# CPU_ETH_RGMII1_SW.net
KiCad netlist of a schematic drawn in Altium Designer
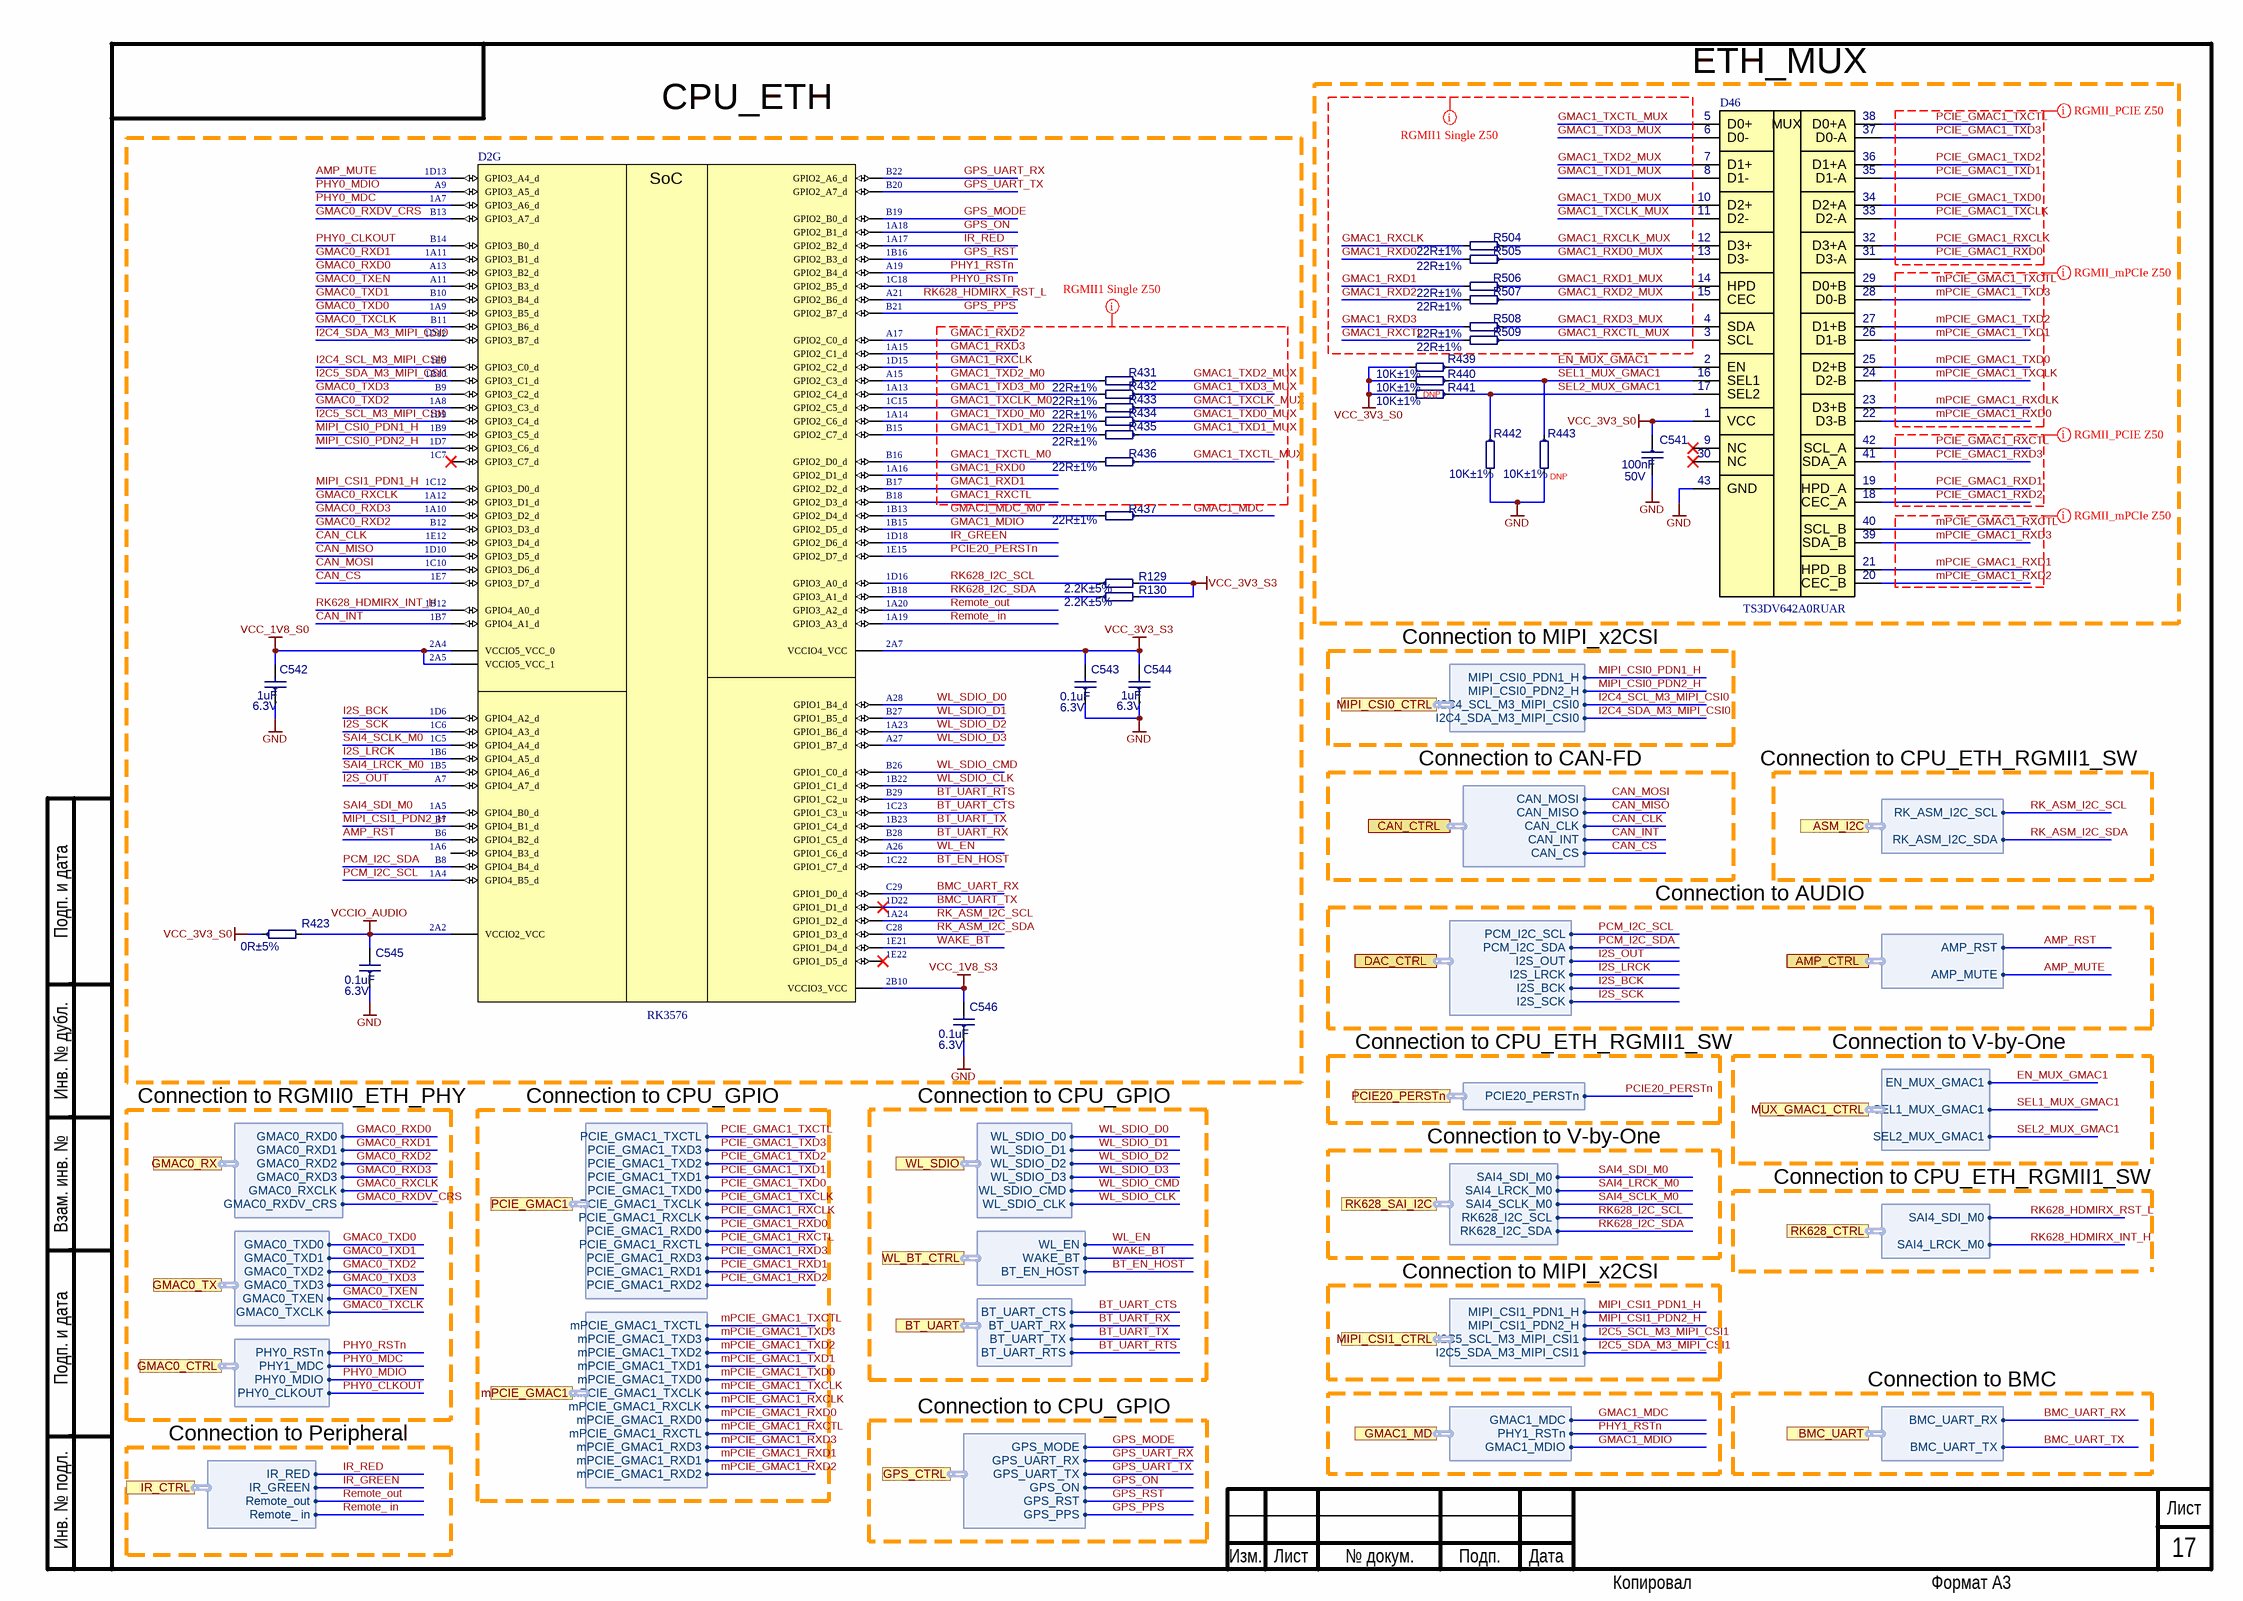
[diagram p0: CPU_ETH_RGMII1_SW.SchDoc]

(export (version "E")
  (design (tool "Eeschema 10.0.6"))
  (components
    (comp (ref "C541")
      (value "100nF")
      (footprint "C0402")
      (description "Ceramic Capacitor 0402 100nF ±10% 50V X7R")
      (fields
        (field (name "VOLTAGE") "50V")
        (field (name "PART NUMBER") "0402-X7R-50V-0.1uF±10%")
        (field (name "TOLERANCE") "10%")
      )
      (libsource (lib "ATB") (part "C"))
    )
    (comp (ref "C542")
      (value "1uF")
      (footprint "C0201")
      (fields
        (field (name "VOLTAGE") "6.3V")
        (field (name "PART NUMBER") "0201-X5R-6.3V-1uF±20%")
        (field (name "TOLERANCE") "20%")
        (field (name "MANUFACTURER") "Murata Electronics")
      )
      (libsource (lib "ATB") (part "C"))
    )
    (comp (ref "C543")
      (value "0.1uF")
      (footprint "C0201")
      (fields
        (field (name "VOLTAGE") "6.3V")
        (field (name "PART NUMBER") "0201-X5R-6.3V-0.1uF±10%")
        (field (name "TOLERANCE") "10%")
        (field (name "MANUFACTURER") "Yageo")
      )
      (libsource (lib "ATB") (part "C"))
    )
    (comp (ref "C544")
      (value "1uF")
      (footprint "C0201")
      (fields
        (field (name "VOLTAGE") "6.3V")
        (field (name "PART NUMBER") "0201-X5R-6.3V-1uF±20%")
        (field (name "TOLERANCE") "20%")
        (field (name "MANUFACTURER") "Murata Electronics")
      )
      (libsource (lib "ATB") (part "C"))
    )
    (comp (ref "C545")
      (value "0.1uF")
      (footprint "C0201")
      (fields
        (field (name "VOLTAGE") "6.3V")
        (field (name "PART NUMBER") "0201-X5R-6.3V-0.1uF±10%")
        (field (name "TOLERANCE") "10%")
        (field (name "MANUFACTURER") "Yageo")
      )
      (libsource (lib "ATB") (part "C"))
    )
    (comp (ref "C546")
      (value "0.1uF")
      (footprint "C0201")
      (fields
        (field (name "VOLTAGE") "6.3V")
        (field (name "PART NUMBER") "0201-X5R-6.3V-0.1uF±10%")
        (field (name "TOLERANCE") "10%")
        (field (name "MANUFACTURER") "Yageo")
      )
      (libsource (lib "ATB") (part "C"))
    )
    (comp (ref "D2")
      (value "RK3576")
      (footprint "BGAFCCSP698L")
      (description "SoC 4xCortex-A72@2.2Ghz+4xCortex-A53@2Ghz, LPDDR4/4X/5/5X, SDIO/eMMC/UFS/FSPI, BGA 16.1x17.2x1.0mm")
      (fields (field (name "MANUFACTURER") "Rockship"))
      (libsource (lib "ATB") (part "RK3576"))
    )
    (comp (ref "D46")
      (value "TS3DV642A0RUAR")
      (footprint "TS3DV642A0RUAR")
      (description "6-Gbps 12-channel differential 1-to-2 and 2-to-1 mux for DVI 1.0/ DisplayPort 1.4 /HDMI 2.0")
      (fields (field (name "MANUFACTURER") "TI"))
      (libsource (lib "LIB_RK") (part "TS3DV642A0RUAR"))
    )
    (comp (ref "R129")
      (value "2.2K±5%")
      (footprint "R0402")
      (fields
        (field (name "PART NUMBER") "0402-0.0625W-2.2K-100ppm±5%")
        (field (name "TOLERANCE") "5%")
        (field (name "MANUFACTURER") "Yageo")
      )
      (libsource (lib "ATB") (part "R"))
    )
    (comp (ref "R130")
      (value "2.2K±5%")
      (footprint "R0402")
      (fields
        (field (name "PART NUMBER") "0402-0.0625W-2.2K-100ppm±5%")
        (field (name "TOLERANCE") "5%")
        (field (name "MANUFACTURER") "Yageo")
      )
      (libsource (lib "ATB") (part "R"))
    )
    (comp (ref "R423")
      (value "0R±5%")
      (footprint "R0402")
      (fields
        (field (name "PART NUMBER") "0402-0.0625W-0R-100ppm±5%")
        (field (name "TOLERANCE") "5%")
        (field (name "MANUFACTURER") "Yageo")
      )
      (libsource (lib "ATB") (part "R"))
    )
    (comp (ref "R431")
      (value "22R±1%")
      (footprint "R0402")
      (description "Chip Resistor 0402 22Ω ±1% 50V ±100ppm/℃ Thick Film")
      (fields (field (name "PART NUMBER") "0402-0.0625W-22R-100ppm±1%") (field (name "TOLERANCE") "1%"))
      (libsource (lib "ATB") (part "R"))
    )
    (comp (ref "R432")
      (value "22R±1%")
      (footprint "R0402")
      (description "Chip Resistor 0402 22Ω ±1% 50V ±100ppm/℃ Thick Film")
      (fields (field (name "PART NUMBER") "0402-0.0625W-22R-100ppm±1%") (field (name "TOLERANCE") "1%"))
      (libsource (lib "ATB") (part "R"))
    )
    (comp (ref "R433")
      (value "22R±1%")
      (footprint "R0402")
      (description "Chip Resistor 0402 22Ω ±1% 50V ±100ppm/℃ Thick Film")
      (fields (field (name "PART NUMBER") "0402-0.0625W-22R-100ppm±1%") (field (name "TOLERANCE") "1%"))
      (libsource (lib "ATB") (part "R"))
    )
    (comp (ref "R434")
      (value "22R±1%")
      (footprint "R0402")
      (description "Chip Resistor 0402 22Ω ±1% 50V ±100ppm/℃ Thick Film")
      (fields (field (name "PART NUMBER") "0402-0.0625W-22R-100ppm±1%") (field (name "TOLERANCE") "1%"))
      (libsource (lib "ATB") (part "R"))
    )
    (comp (ref "R435")
      (value "22R±1%")
      (footprint "R0402")
      (description "Chip Resistor 0402 22Ω ±1% 50V ±100ppm/℃ Thick Film")
      (fields (field (name "PART NUMBER") "0402-0.0625W-22R-100ppm±1%") (field (name "TOLERANCE") "1%"))
      (libsource (lib "ATB") (part "R"))
    )
    (comp (ref "R436")
      (value "22R±1%")
      (footprint "R0402")
      (description "Chip Resistor 0402 22Ω ±1% 50V ±100ppm/℃ Thick Film")
      (fields (field (name "PART NUMBER") "0402-0.0625W-22R-100ppm±1%") (field (name "TOLERANCE") "1%"))
      (libsource (lib "ATB") (part "R"))
    )
    (comp (ref "R437")
      (value "22R±1%")
      (footprint "R0402")
      (description "Chip Resistor 0402 22Ω ±1% 50V ±100ppm/℃ Thick Film")
      (fields (field (name "PART NUMBER") "0402-0.0625W-22R-100ppm±1%") (field (name "TOLERANCE") "1%"))
      (libsource (lib "ATB") (part "R"))
    )
    (comp (ref "R439")
      (value "10K±1%")
      (footprint "R0402")
      (description "Chip Resistor 0402 10kΩ ±1% 50V ±100ppm/℃ Thick Film")
      (fields (field (name "PART NUMBER") "0402-0.0625W-10K-100ppm±1%") (field (name "TOLERANCE") "1%"))
      (libsource (lib "ATB") (part "R"))
    )
    (comp (ref "R440")
      (value "10K±1%")
      (footprint "R0402")
      (description "Chip Resistor 0402 10kΩ ±1% 50V ±100ppm/℃ Thick Film")
      (fields (field (name "PART NUMBER") "0402-0.0625W-10K-100ppm±1%") (field (name "TOLERANCE") "1%"))
      (libsource (lib "ATB") (part "R"))
    )
    (comp (ref "R441")
      (value "10K±1%")
      (footprint "R0402")
      (description "Chip Resistor 0402 10kΩ ±1% 50V ±100ppm/℃ Thick Film")
      (fields (field (name "PART NUMBER") "0402-0.0625W-10K-100ppm±1%") (field (name "TOLERANCE") "1%"))
      (libsource (lib "ATB") (part "R"))
    )
    (comp (ref "R442")
      (value "10K±1%")
      (footprint "R0402")
      (description "Chip Resistor 0402 10kΩ ±1% 50V ±100ppm/℃ Thick Film")
      (fields (field (name "PART NUMBER") "0402-0.0625W-10K-100ppm±1%") (field (name "TOLERANCE") "1%"))
      (libsource (lib "ATB") (part "R"))
    )
    (comp (ref "R443")
      (value "10K±1%")
      (footprint "R0402")
      (description "Chip Resistor 0402 10kΩ ±1% 50V ±100ppm/℃ Thick Film")
      (fields (field (name "PART NUMBER") "0402-0.0625W-10K-100ppm±1%") (field (name "TOLERANCE") "1%"))
      (libsource (lib "ATB") (part "R"))
    )
    (comp (ref "R504")
      (value "22R±1%")
      (footprint "R0402")
      (description "Chip Resistor 0402 22Ω ±1% 50V ±100ppm/℃ Thick Film")
      (fields (field (name "PART NUMBER") "0402-0.0625W-22R-100ppm±1%") (field (name "TOLERANCE") "1%"))
      (libsource (lib "ATB") (part "R"))
    )
    (comp (ref "R505")
      (value "22R±1%")
      (footprint "R0402")
      (description "Chip Resistor 0402 22Ω ±1% 50V ±100ppm/℃ Thick Film")
      (fields (field (name "PART NUMBER") "0402-0.0625W-22R-100ppm±1%") (field (name "TOLERANCE") "1%"))
      (libsource (lib "ATB") (part "R"))
    )
    (comp (ref "R506")
      (value "22R±1%")
      (footprint "R0402")
      (description "Chip Resistor 0402 22Ω ±1% 50V ±100ppm/℃ Thick Film")
      (fields (field (name "PART NUMBER") "0402-0.0625W-22R-100ppm±1%") (field (name "TOLERANCE") "1%"))
      (libsource (lib "ATB") (part "R"))
    )
    (comp (ref "R507")
      (value "22R±1%")
      (footprint "R0402")
      (description "Chip Resistor 0402 22Ω ±1% 50V ±100ppm/℃ Thick Film")
      (fields (field (name "PART NUMBER") "0402-0.0625W-22R-100ppm±1%") (field (name "TOLERANCE") "1%"))
      (libsource (lib "ATB") (part "R"))
    )
    (comp (ref "R508")
      (value "22R±1%")
      (footprint "R0402")
      (description "Chip Resistor 0402 22Ω ±1% 50V ±100ppm/℃ Thick Film")
      (fields (field (name "PART NUMBER") "0402-0.0625W-22R-100ppm±1%") (field (name "TOLERANCE") "1%"))
      (libsource (lib "ATB") (part "R"))
    )
    (comp (ref "R509")
      (value "22R±1%")
      (footprint "R0402")
      (description "Chip Resistor 0402 22Ω ±1% 50V ±100ppm/℃ Thick Film")
      (fields (field (name "PART NUMBER") "0402-0.0625W-22R-100ppm±1%") (field (name "TOLERANCE") "1%"))
      (libsource (lib "ATB") (part "R"))
    )
  )
  (nets
    (net (code "22") (name "/AMP_MUTE") (class "Default")
      (node (ref "D2") (pin "1D13") (pinfunction "GPIO3_A4_d_1D13") (pintype "bidirectional"))
    )
    (net (code "23") (name "/AMP_RST") (class "Default")
      (node (ref "D2") (pin "B6") (pinfunction "GPIO4_B2_d_B6") (pintype "bidirectional"))
    )
    (net (code "24") (name "/BMC_UART_RX") (class "Default")
      (node (ref "D2") (pin "C29") (pinfunction "GPIO1_D0_d_C29") (pintype "bidirectional"))
    )
    (net (code "25") (name "/BMC_UART_TX") (class "Default")
      (node (ref "D2") (pin "1D22") (pinfunction "GPIO1_D1_d_1D22") (pintype "bidirectional+no_connect"))
    )
    (net (code "26") (name "/BT_EN_HOST") (class "Default")
      (node (ref "D2") (pin "1C22") (pinfunction "GPIO1_C7_d_1C22") (pintype "bidirectional"))
    )
    (net (code "27") (name "/BT_UART_CTS") (class "Default")
      (node (ref "D2") (pin "1C23") (pinfunction "GPIO1_C3_u_1C23") (pintype "bidirectional"))
    )
    (net (code "28") (name "/BT_UART_RTS") (class "Default")
      (node (ref "D2") (pin "B29") (pinfunction "GPIO1_C2_u_B29") (pintype "bidirectional"))
    )
    (net (code "29") (name "/BT_UART_RX") (class "Default")
      (node (ref "D2") (pin "B28") (pinfunction "GPIO1_C5_d_B28") (pintype "bidirectional"))
    )
    (net (code "30") (name "/BT_UART_TX") (class "Default")
      (node (ref "D2") (pin "1B23") (pinfunction "GPIO1_C4_d_1B23") (pintype "bidirectional"))
    )
    (net (code "31") (name "/CAN_CLK") (class "Default")
      (node (ref "D2") (pin "1E12") (pinfunction "GPIO3_D4_d_1E12") (pintype "bidirectional"))
    )
    (net (code "32") (name "/CAN_CS") (class "Default")
      (node (ref "D2") (pin "1E7") (pinfunction "GPIO3_D7_d_1E7") (pintype "bidirectional"))
    )
    (net (code "33") (name "/CAN_INT") (class "Default")
      (node (ref "D2") (pin "1B7") (pinfunction "GPIO4_A1_d_1B7") (pintype "bidirectional"))
    )
    (net (code "34") (name "/CAN_MISO") (class "Default")
      (node (ref "D2") (pin "1D10") (pinfunction "GPIO3_D5_d_1D10") (pintype "bidirectional"))
    )
    (net (code "35") (name "/CAN_MOSI") (class "Default")
      (node (ref "D2") (pin "1C10") (pinfunction "GPIO3_D6_d_1C10") (pintype "bidirectional"))
    )
    (net (code "36") (name "/EN_MUX_GMAC1") (class "Default")
      (node (ref "D46") (pin "2") (pinfunction "EN_2") (pintype "passive"))
      (node (ref "R439") (pin "1") (pinfunction "1_1") (pintype "passive"))
    )
    (net (code "37") (name "/GMAC0_RXCLK") (class "Default")
      (node (ref "D2") (pin "1A12") (pinfunction "GPIO3_D1_d_1A12") (pintype "bidirectional"))
    )
    (net (code "38") (name "/GMAC0_RXD0") (class "Default")
      (node (ref "D2") (pin "A13") (pinfunction "GPIO3_B2_d_A13") (pintype "bidirectional"))
    )
    (net (code "39") (name "/GMAC0_RXD1") (class "Default")
      (node (ref "D2") (pin "1A11") (pinfunction "GPIO3_B1_d_1A11") (pintype "bidirectional"))
    )
    (net (code "40") (name "/GMAC0_RXD2") (class "Default")
      (node (ref "D2") (pin "B12") (pinfunction "GPIO3_D3_d_B12") (pintype "bidirectional"))
    )
    (net (code "41") (name "/GMAC0_RXD3") (class "Default")
      (node (ref "D2") (pin "1A10") (pinfunction "GPIO3_D2_d_1A10") (pintype "bidirectional"))
    )
    (net (code "42") (name "/GMAC0_RXDV_CRS") (class "Default")
      (node (ref "D2") (pin "B13") (pinfunction "GPIO3_A7_d_B13") (pintype "bidirectional"))
    )
    (net (code "43") (name "/GMAC0_TXCLK") (class "Default")
      (node (ref "D2") (pin "B11") (pinfunction "GPIO3_B6_d_B11") (pintype "bidirectional"))
    )
    (net (code "44") (name "/GMAC0_TXD0") (class "Default")
      (node (ref "D2") (pin "1A9") (pinfunction "GPIO3_B5_d_1A9") (pintype "bidirectional"))
    )
    (net (code "45") (name "/GMAC0_TXD1") (class "Default")
      (node (ref "D2") (pin "B10") (pinfunction "GPIO3_B4_d_B10") (pintype "bidirectional"))
    )
    (net (code "46") (name "/GMAC0_TXD2") (class "Default")
      (node (ref "D2") (pin "1A8") (pinfunction "GPIO3_C3_d_1A8") (pintype "bidirectional"))
    )
    (net (code "47") (name "/GMAC0_TXD3") (class "Default")
      (node (ref "D2") (pin "B9") (pinfunction "GPIO3_C2_d_B9") (pintype "bidirectional"))
    )
    (net (code "48") (name "/GMAC0_TXEN") (class "Default")
      (node (ref "D2") (pin "A11") (pinfunction "GPIO3_B3_d_A11") (pintype "bidirectional"))
    )
    (net (code "49") (name "/GMAC1_MDC") (class "Default")
      (node (ref "R437") (pin "1") (pinfunction "1_1") (pintype "passive"))
    )
    (net (code "50") (name "/GMAC1_MDC_M0") (class "Default")
      (node (ref "D2") (pin "1B13") (pinfunction "GPIO2_D4_d_1B13") (pintype "bidirectional"))
      (node (ref "R437") (pin "2") (pinfunction "2_2") (pintype "passive"))
    )
    (net (code "51") (name "/GMAC1_MDIO") (class "Default")
      (node (ref "D2") (pin "1B15") (pinfunction "GPIO2_D5_d_1B15") (pintype "bidirectional"))
    )
    (net (code "52") (name "/GMAC1_RXCLK") (class "Default")
      (node (ref "D2") (pin "1D15") (pinfunction "GPIO2_C2_d_1D15") (pintype "bidirectional"))
      (node (ref "R504") (pin "2") (pinfunction "2_2") (pintype "passive"))
    )
    (net (code "53") (name "/GMAC1_RXCLK_MUX") (class "Default")
      (node (ref "D46") (pin "12") (pinfunction "D3+_12") (pintype "passive"))
      (node (ref "R504") (pin "1") (pinfunction "1_1") (pintype "passive"))
    )
    (net (code "54") (name "/GMAC1_RXCTL") (class "Default")
      (node (ref "D2") (pin "B18") (pinfunction "GPIO2_D3_d_B18") (pintype "bidirectional"))
      (node (ref "R509") (pin "2") (pinfunction "2_2") (pintype "passive"))
    )
    (net (code "55") (name "/GMAC1_RXCTL_MUX") (class "Default")
      (node (ref "D46") (pin "3") (pinfunction "SCL_3") (pintype "passive"))
      (node (ref "R509") (pin "1") (pinfunction "1_1") (pintype "passive"))
    )
    (net (code "56") (name "/GMAC1_RXD0") (class "Default")
      (node (ref "D2") (pin "1A16") (pinfunction "GPIO2_D1_d_1A16") (pintype "bidirectional"))
      (node (ref "R505") (pin "2") (pinfunction "2_2") (pintype "passive"))
    )
    (net (code "57") (name "/GMAC1_RXD0_MUX") (class "Default")
      (node (ref "D46") (pin "13") (pinfunction "D3-_13") (pintype "passive"))
      (node (ref "R505") (pin "1") (pinfunction "1_1") (pintype "passive"))
    )
    (net (code "58") (name "/GMAC1_RXD1") (class "Default")
      (node (ref "D2") (pin "B17") (pinfunction "GPIO2_D2_d_B17") (pintype "bidirectional"))
      (node (ref "R506") (pin "2") (pinfunction "2_2") (pintype "passive"))
    )
    (net (code "59") (name "/GMAC1_RXD1_MUX") (class "Default")
      (node (ref "D46") (pin "14") (pinfunction "HPD_14") (pintype "passive"))
      (node (ref "R506") (pin "1") (pinfunction "1_1") (pintype "passive"))
    )
    (net (code "60") (name "/GMAC1_RXD2") (class "Default")
      (node (ref "D2") (pin "A17") (pinfunction "GPIO2_C0_d_A17") (pintype "bidirectional"))
      (node (ref "R507") (pin "2") (pinfunction "2_2") (pintype "passive"))
    )
    (net (code "61") (name "/GMAC1_RXD2_MUX") (class "Default")
      (node (ref "D46") (pin "15") (pinfunction "CEC_15") (pintype "passive"))
      (node (ref "R507") (pin "1") (pinfunction "1_1") (pintype "passive"))
    )
    (net (code "62") (name "/GMAC1_RXD3") (class "Default")
      (node (ref "D2") (pin "1A15") (pinfunction "GPIO2_C1_d_1A15") (pintype "bidirectional"))
      (node (ref "R508") (pin "2") (pinfunction "2_2") (pintype "passive"))
    )
    (net (code "63") (name "/GMAC1_RXD3_MUX") (class "Default")
      (node (ref "D46") (pin "4") (pinfunction "SDA_4") (pintype "passive"))
      (node (ref "R508") (pin "1") (pinfunction "1_1") (pintype "passive"))
    )
    (net (code "64") (name "/GMAC1_TXCLK_M0") (class "Default")
      (node (ref "D2") (pin "1C15") (pinfunction "GPIO2_C5_d_1C15") (pintype "bidirectional"))
      (node (ref "R433") (pin "2") (pinfunction "2_2") (pintype "passive"))
    )
    (net (code "65") (name "/GMAC1_TXCLK_MUX") (class "Default")
      (node (ref "D46") (pin "11") (pinfunction "D2-_11") (pintype "passive"))
      (node (ref "R433") (pin "1") (pinfunction "1_1") (pintype "passive"))
    )
    (net (code "66") (name "/GMAC1_TXCTL_M0") (class "Default")
      (node (ref "D2") (pin "B16") (pinfunction "GPIO2_D0_d_B16") (pintype "bidirectional"))
      (node (ref "R436") (pin "2") (pinfunction "2_2") (pintype "passive"))
    )
    (net (code "67") (name "/GMAC1_TXCTL_MUX") (class "Default")
      (node (ref "D46") (pin "5") (pinfunction "D0+_5") (pintype "passive"))
      (node (ref "R436") (pin "1") (pinfunction "1_1") (pintype "passive"))
    )
    (net (code "68") (name "/GMAC1_TXD0_M0") (class "Default")
      (node (ref "D2") (pin "1A14") (pinfunction "GPIO2_C6_d_1A14") (pintype "bidirectional"))
      (node (ref "R434") (pin "2") (pinfunction "2_2") (pintype "passive"))
    )
    (net (code "69") (name "/GMAC1_TXD0_MUX") (class "Default")
      (node (ref "D46") (pin "10") (pinfunction "D2+_10") (pintype "passive"))
      (node (ref "R434") (pin "1") (pinfunction "1_1") (pintype "passive"))
    )
    (net (code "70") (name "/GMAC1_TXD1_M0") (class "Default")
      (node (ref "D2") (pin "B15") (pinfunction "GPIO2_C7_d_B15") (pintype "bidirectional"))
      (node (ref "R435") (pin "2") (pinfunction "2_2") (pintype "passive"))
    )
    (net (code "71") (name "/GMAC1_TXD1_MUX") (class "Default")
      (node (ref "D46") (pin "8") (pinfunction "D1-_8") (pintype "passive"))
      (node (ref "R435") (pin "1") (pinfunction "1_1") (pintype "passive"))
    )
    (net (code "72") (name "/GMAC1_TXD2_M0") (class "Default")
      (node (ref "D2") (pin "A15") (pinfunction "GPIO2_C3_d_A15") (pintype "bidirectional"))
      (node (ref "R431") (pin "2") (pinfunction "2_2") (pintype "passive"))
    )
    (net (code "73") (name "/GMAC1_TXD2_MUX") (class "Default")
      (node (ref "D46") (pin "7") (pinfunction "D1+_7") (pintype "passive"))
      (node (ref "R431") (pin "1") (pinfunction "1_1") (pintype "passive"))
    )
    (net (code "74") (name "/GMAC1_TXD3_M0") (class "Default")
      (node (ref "D2") (pin "1A13") (pinfunction "GPIO2_C4_d_1A13") (pintype "bidirectional"))
      (node (ref "R432") (pin "2") (pinfunction "2_2") (pintype "passive"))
    )
    (net (code "75") (name "/GMAC1_TXD3_MUX") (class "Default")
      (node (ref "D46") (pin "6") (pinfunction "D0-_6") (pintype "passive"))
      (node (ref "R432") (pin "1") (pinfunction "1_1") (pintype "passive"))
    )
    (net (code "76") (name "/GPS_MODE") (class "Default")
      (node (ref "D2") (pin "B19") (pinfunction "GPIO2_B0_d_B19") (pintype "bidirectional"))
    )
    (net (code "77") (name "/GPS_ON") (class "Default")
      (node (ref "D2") (pin "1A18") (pinfunction "GPIO2_B1_d_1A18") (pintype "bidirectional"))
    )
    (net (code "78") (name "/GPS_PPS") (class "Default")
      (node (ref "D2") (pin "B21") (pinfunction "GPIO2_B7_d_B21") (pintype "bidirectional"))
    )
    (net (code "79") (name "/GPS_RST") (class "Default")
      (node (ref "D2") (pin "1B16") (pinfunction "GPIO2_B3_d_1B16") (pintype "bidirectional"))
    )
    (net (code "80") (name "/GPS_UART_RX") (class "Default")
      (node (ref "D2") (pin "B22") (pinfunction "GPIO2_A6_d_B22") (pintype "bidirectional"))
    )
    (net (code "81") (name "/GPS_UART_TX") (class "Default")
      (node (ref "D2") (pin "B20") (pinfunction "GPIO2_A7_d_B20") (pintype "bidirectional"))
    )
    (net (code "82") (name "/I2C4_SCL_M3_MIPI_CSI0") (class "Default")
      (node (ref "D2") (pin "1E9") (pinfunction "GPIO3_C0_d_1E9") (pintype "bidirectional"))
    )
    (net (code "83") (name "/I2C4_SDA_M3_MIPI_CSI0") (class "Default")
      (node (ref "D2") (pin "1D12") (pinfunction "GPIO3_B7_d_1D12") (pintype "bidirectional"))
    )
    (net (code "84") (name "/I2C5_SCL_M3_MIPI_CSI1") (class "Default")
      (node (ref "D2") (pin "1D9") (pinfunction "GPIO3_C4_d_1D9") (pintype "bidirectional"))
    )
    (net (code "85") (name "/I2C5_SDA_M3_MIPI_CSI1") (class "Default")
      (node (ref "D2") (pin "1B10") (pinfunction "GPIO3_C1_d_1B10") (pintype "bidirectional"))
    )
    (net (code "86") (name "/I2S_BCK") (class "Default")
      (node (ref "D2") (pin "1D6") (pinfunction "GPIO4_A2_d_1D6") (pintype "bidirectional"))
    )
    (net (code "87") (name "/I2S_LRCK") (class "Default")
      (node (ref "D2") (pin "1B6") (pinfunction "GPIO4_A5_d_1B6") (pintype "bidirectional"))
    )
    (net (code "88") (name "/I2S_OUT") (class "Default")
      (node (ref "D2") (pin "A7") (pinfunction "GPIO4_A7_d_A7") (pintype "bidirectional"))
    )
    (net (code "89") (name "/I2S_SCK") (class "Default")
      (node (ref "D2") (pin "1C6") (pinfunction "GPIO4_A3_d_1C6") (pintype "bidirectional"))
    )
    (net (code "90") (name "/IR_GREEN") (class "Default")
      (node (ref "D2") (pin "1D18") (pinfunction "GPIO2_D6_d_1D18") (pintype "bidirectional"))
    )
    (net (code "91") (name "/IR_RED") (class "Default")
      (node (ref "D2") (pin "1A17") (pinfunction "GPIO2_B2_d_1A17") (pintype "bidirectional"))
    )
    (net (code "92") (name "/MIPI_CSI0_PDN1_H") (class "Default")
      (node (ref "D2") (pin "1B9") (pinfunction "GPIO3_C5_d_1B9") (pintype "bidirectional"))
    )
    (net (code "93") (name "/MIPI_CSI0_PDN2_H") (class "Default")
      (node (ref "D2") (pin "1D7") (pinfunction "GPIO3_C6_d_1D7") (pintype "bidirectional"))
    )
    (net (code "94") (name "/MIPI_CSI1_PDN1_H") (class "Default")
      (node (ref "D2") (pin "1C12") (pinfunction "GPIO3_D0_d_1C12") (pintype "bidirectional"))
    )
    (net (code "95") (name "/MIPI_CSI1_PDN2_H") (class "Default")
      (node (ref "D2") (pin "B7") (pinfunction "GPIO4_B1_d_B7") (pintype "bidirectional"))
    )
    (net (code "96") (name "/PCIE20_PERSTn") (class "Default")
      (node (ref "D2") (pin "1E15") (pinfunction "GPIO2_D7_d_1E15") (pintype "bidirectional"))
    )
    (net (code "97") (name "/PCIE_GMAC1_RXCLK") (class "Default")
      (node (ref "D46") (pin "32") (pinfunction "D3+A_32") (pintype "passive"))
    )
    (net (code "98") (name "/PCIE_GMAC1_RXCTL") (class "Default")
      (node (ref "D46") (pin "42") (pinfunction "SCL_A_42") (pintype "passive"))
    )
    (net (code "99") (name "/PCIE_GMAC1_RXD0") (class "Default")
      (node (ref "D46") (pin "31") (pinfunction "D3-A_31") (pintype "passive"))
    )
    (net (code "100") (name "/PCIE_GMAC1_RXD1") (class "Default")
      (node (ref "D46") (pin "19") (pinfunction "HPD_A_19") (pintype "passive"))
    )
    (net (code "101") (name "/PCIE_GMAC1_RXD2") (class "Default")
      (node (ref "D46") (pin "18") (pinfunction "CEC_A_18") (pintype "passive"))
    )
    (net (code "102") (name "/PCIE_GMAC1_RXD3") (class "Default")
      (node (ref "D46") (pin "41") (pinfunction "SDA_A_41") (pintype "passive"))
    )
    (net (code "103") (name "/PCIE_GMAC1_TXCLK") (class "Default")
      (node (ref "D46") (pin "33") (pinfunction "D2-A_33") (pintype "passive"))
    )
    (net (code "104") (name "/PCIE_GMAC1_TXCTL") (class "Default")
      (node (ref "D46") (pin "38") (pinfunction "D0+A_38") (pintype "passive"))
    )
    (net (code "105") (name "/PCIE_GMAC1_TXD0") (class "Default")
      (node (ref "D46") (pin "34") (pinfunction "D2+A_34") (pintype "passive"))
    )
    (net (code "106") (name "/PCIE_GMAC1_TXD1") (class "Default")
      (node (ref "D46") (pin "35") (pinfunction "D1-A_35") (pintype "passive"))
    )
    (net (code "107") (name "/PCIE_GMAC1_TXD2") (class "Default")
      (node (ref "D46") (pin "36") (pinfunction "D1+A_36") (pintype "passive"))
    )
    (net (code "108") (name "/PCIE_GMAC1_TXD3") (class "Default")
      (node (ref "D46") (pin "37") (pinfunction "D0-A_37") (pintype "passive"))
    )
    (net (code "109") (name "/PCM_I2C_SCL") (class "Default")
      (node (ref "D2") (pin "1A4") (pinfunction "GPIO4_B5_d_1A4") (pintype "bidirectional"))
    )
    (net (code "110") (name "/PCM_I2C_SDA") (class "Default")
      (node (ref "D2") (pin "B8") (pinfunction "GPIO4_B4_d_B8") (pintype "bidirectional"))
    )
    (net (code "111") (name "/PHY0_CLKOUT") (class "Default")
      (node (ref "D2") (pin "B14") (pinfunction "GPIO3_B0_d_B14") (pintype "bidirectional"))
    )
    (net (code "112") (name "/PHY0_MDC") (class "Default")
      (node (ref "D2") (pin "1A7") (pinfunction "GPIO3_A6_d_1A7") (pintype "bidirectional"))
    )
    (net (code "113") (name "/PHY0_MDIO") (class "Default")
      (node (ref "D2") (pin "A9") (pinfunction "GPIO3_A5_d_A9") (pintype "bidirectional"))
    )
    (net (code "114") (name "/PHY0_RSTn") (class "Default")
      (node (ref "D2") (pin "1C18") (pinfunction "GPIO2_B5_d_1C18") (pintype "bidirectional"))
    )
    (net (code "115") (name "/PHY1_RSTn") (class "Default")
      (node (ref "D2") (pin "A19") (pinfunction "GPIO2_B4_d_A19") (pintype "bidirectional"))
    )
    (net (code "116") (name "/RK628_HDMIRX_INT_H") (class "Default")
      (node (ref "D2") (pin "1B12") (pinfunction "GPIO4_A0_d_1B12") (pintype "bidirectional"))
    )
    (net (code "117") (name "/RK628_HDMIRX_RST_L") (class "Default")
      (node (ref "D2") (pin "A21") (pinfunction "GPIO2_B6_d_A21") (pintype "bidirectional"))
    )
    (net (code "118") (name "/RK628_I2C_SCL") (class "Default")
      (node (ref "D2") (pin "1D16") (pinfunction "GPIO3_A0_d_1D16") (pintype "bidirectional"))
      (node (ref "R129") (pin "1") (pinfunction "1_1") (pintype "passive"))
    )
    (net (code "119") (name "/RK628_I2C_SDA") (class "Default")
      (node (ref "D2") (pin "1B18") (pinfunction "GPIO3_A1_d_1B18") (pintype "bidirectional"))
      (node (ref "R130") (pin "1") (pinfunction "1_1") (pintype "passive"))
    )
    (net (code "120") (name "/RK_ASM_I2C_SCL") (class "Default")
      (node (ref "D2") (pin "1A24") (pinfunction "GPIO1_D2_d_1A24") (pintype "bidirectional"))
    )
    (net (code "121") (name "/RK_ASM_I2C_SDA") (class "Default")
      (node (ref "D2") (pin "C28") (pinfunction "GPIO1_D3_d_C28") (pintype "bidirectional"))
    )
    (net (code "122") (name "/Remote_ in") (class "Default")
      (node (ref "D2") (pin "1A19") (pinfunction "GPIO3_A3_d_1A19") (pintype "bidirectional"))
    )
    (net (code "123") (name "/Remote_out") (class "Default")
      (node (ref "D2") (pin "1A20") (pinfunction "GPIO3_A2_d_1A20") (pintype "bidirectional"))
    )
    (net (code "124") (name "/SAI4_LRCK_M0") (class "Default")
      (node (ref "D2") (pin "1B5") (pinfunction "GPIO4_A6_d_1B5") (pintype "bidirectional"))
    )
    (net (code "125") (name "/SAI4_SCLK_M0") (class "Default")
      (node (ref "D2") (pin "1C5") (pinfunction "GPIO4_A4_d_1C5") (pintype "bidirectional"))
    )
    (net (code "126") (name "/SAI4_SDI_M0") (class "Default")
      (node (ref "D2") (pin "1A5") (pinfunction "GPIO4_B0_d_1A5") (pintype "bidirectional"))
    )
    (net (code "127") (name "/SEL1_MUX_GMAC1") (class "Default")
      (node (ref "D46") (pin "16") (pinfunction "SEL1_16") (pintype "passive"))
      (node (ref "R440") (pin "1") (pinfunction "1_1") (pintype "passive"))
      (node (ref "R443") (pin "1") (pinfunction "1_1") (pintype "passive"))
    )
    (net (code "128") (name "/SEL2_MUX_GMAC1") (class "Default")
      (node (ref "D46") (pin "17") (pinfunction "SEL2_17") (pintype "passive"))
      (node (ref "R441") (pin "1") (pinfunction "1_1") (pintype "passive"))
      (node (ref "R442") (pin "1") (pinfunction "1_1") (pintype "passive"))
    )
    (net (code "129") (name "/WAKE_BT") (class "Default")
      (node (ref "D2") (pin "1E21") (pinfunction "GPIO1_D4_d_1E21") (pintype "bidirectional"))
    )
    (net (code "130") (name "/WL_EN") (class "Default")
      (node (ref "D2") (pin "A26") (pinfunction "GPIO1_C6_d_A26") (pintype "bidirectional"))
    )
    (net (code "131") (name "/WL_SDIO_CLK") (class "Default")
      (node (ref "D2") (pin "1B22") (pinfunction "GPIO1_C1_d_1B22") (pintype "bidirectional"))
    )
    (net (code "132") (name "/WL_SDIO_CMD") (class "Default")
      (node (ref "D2") (pin "B26") (pinfunction "GPIO1_C0_d_B26") (pintype "bidirectional"))
    )
    (net (code "133") (name "/WL_SDIO_D0") (class "Default")
      (node (ref "D2") (pin "A28") (pinfunction "GPIO1_B4_d_A28") (pintype "bidirectional"))
    )
    (net (code "134") (name "/WL_SDIO_D1") (class "Default")
      (node (ref "D2") (pin "B27") (pinfunction "GPIO1_B5_d_B27") (pintype "bidirectional"))
    )
    (net (code "135") (name "/WL_SDIO_D2") (class "Default")
      (node (ref "D2") (pin "1A23") (pinfunction "GPIO1_B6_d_1A23") (pintype "bidirectional"))
    )
    (net (code "136") (name "/WL_SDIO_D3") (class "Default")
      (node (ref "D2") (pin "A27") (pinfunction "GPIO1_B7_d_A27") (pintype "bidirectional"))
    )
    (net (code "137") (name "/mPCIE_GMAC1_RXCLK") (class "Default")
      (node (ref "D46") (pin "23") (pinfunction "D3+B_23") (pintype "passive"))
    )
    (net (code "138") (name "/mPCIE_GMAC1_RXCTL") (class "Default")
      (node (ref "D46") (pin "40") (pinfunction "SCL_B_40") (pintype "passive"))
    )
    (net (code "139") (name "/mPCIE_GMAC1_RXD0") (class "Default")
      (node (ref "D46") (pin "22") (pinfunction "D3-B_22") (pintype "passive"))
    )
    (net (code "140") (name "/mPCIE_GMAC1_RXD1") (class "Default")
      (node (ref "D46") (pin "21") (pinfunction "HPD_B_21") (pintype "passive"))
    )
    (net (code "141") (name "/mPCIE_GMAC1_RXD2") (class "Default")
      (node (ref "D46") (pin "20") (pinfunction "CEC_B_20") (pintype "passive"))
    )
    (net (code "142") (name "/mPCIE_GMAC1_RXD3") (class "Default")
      (node (ref "D46") (pin "39") (pinfunction "SDA_B_39") (pintype "passive"))
    )
    (net (code "143") (name "/mPCIE_GMAC1_TXCLK") (class "Default")
      (node (ref "D46") (pin "24") (pinfunction "D2-B_24") (pintype "passive"))
    )
    (net (code "144") (name "/mPCIE_GMAC1_TXCTL") (class "Default")
      (node (ref "D46") (pin "29") (pinfunction "D0+B_29") (pintype "passive"))
    )
    (net (code "145") (name "/mPCIE_GMAC1_TXD0") (class "Default")
      (node (ref "D46") (pin "25") (pinfunction "D2+B_25") (pintype "passive"))
    )
    (net (code "146") (name "/mPCIE_GMAC1_TXD1") (class "Default")
      (node (ref "D46") (pin "26") (pinfunction "D1-B_26") (pintype "passive"))
    )
    (net (code "147") (name "/mPCIE_GMAC1_TXD2") (class "Default")
      (node (ref "D46") (pin "27") (pinfunction "D1+B_27") (pintype "passive"))
    )
    (net (code "148") (name "/mPCIE_GMAC1_TXD3") (class "Default")
      (node (ref "D46") (pin "28") (pinfunction "D0-B_28") (pintype "passive"))
    )
    (net (code "171") (name "GND") (class "Default")
      (node (ref "C541") (pin "2") (pinfunction "2_2") (pintype "passive"))
      (node (ref "C542") (pin "1") (pinfunction "1_1") (pintype "passive"))
      (node (ref "C543") (pin "1") (pinfunction "1_1") (pintype "passive"))
      (node (ref "C544") (pin "1") (pinfunction "1_1") (pintype "passive"))
      (node (ref "C545") (pin "1") (pinfunction "1_1") (pintype "passive"))
      (node (ref "C546") (pin "1") (pinfunction "1_1") (pintype "passive"))
      (node (ref "D46") (pin "43") (pinfunction "GND_43") (pintype "passive"))
      (node (ref "R442") (pin "2") (pinfunction "2_2") (pintype "passive"))
      (node (ref "R443") (pin "2") (pinfunction "2_2") (pintype "passive"))
    )
    (net (code "172") (name "VCCIO_AUDIO") (class "Default")
      (node (ref "C545") (pin "2") (pinfunction "2_2") (pintype "passive"))
      (node (ref "D2") (pin "2A2") (pinfunction "VCCIO2_VCC_2A2") (pintype "power_in"))
      (node (ref "R423") (pin "2") (pinfunction "2_2") (pintype "passive"))
    )
    (net (code "173") (name "VCC_1V8_S0") (class "Default")
      (node (ref "C542") (pin "2") (pinfunction "2_2") (pintype "passive"))
      (node (ref "D2") (pin "2A4") (pinfunction "VCCIO5_VCC_0_2A4") (pintype "power_in"))
      (node (ref "D2") (pin "2A5") (pinfunction "VCCIO5_VCC_1_2A5") (pintype "power_in"))
    )
    (net (code "174") (name "VCC_1V8_S3") (class "Default")
      (node (ref "C546") (pin "2") (pinfunction "2_2") (pintype "passive"))
      (node (ref "D2") (pin "2B10") (pinfunction "VCCIO3_VCC_2B10") (pintype "power_in"))
    )
    (net (code "175") (name "VCC_3V3_S0") (class "Default")
      (node (ref "C541") (pin "1") (pinfunction "1_1") (pintype "passive"))
      (node (ref "D46") (pin "1") (pinfunction "VCC_1") (pintype "passive"))
      (node (ref "R423") (pin "1") (pinfunction "1_1") (pintype "passive"))
      (node (ref "R439") (pin "2") (pinfunction "2_2") (pintype "passive"))
      (node (ref "R440") (pin "2") (pinfunction "2_2") (pintype "passive"))
      (node (ref "R441") (pin "2") (pinfunction "2_2") (pintype "passive"))
    )
    (net (code "176") (name "VCC_3V3_S3") (class "Default")
      (node (ref "C543") (pin "2") (pinfunction "2_2") (pintype "passive"))
      (node (ref "C544") (pin "2") (pinfunction "2_2") (pintype "passive"))
      (node (ref "D2") (pin "2A7") (pinfunction "VCCIO4_VCC_2A7") (pintype "power_in"))
      (node (ref "R129") (pin "2") (pinfunction "2_2") (pintype "passive"))
      (node (ref "R130") (pin "2") (pinfunction "2_2") (pintype "passive"))
    )
    (net (code "177") (name "unconnected-(D2G-GPIO1_D5_d-Pad1E22)") (class "Default")
      (node (ref "D2") (pin "1E22") (pinfunction "GPIO1_D5_d_1E22") (pintype "bidirectional+no_connect"))
    )
    (net (code "178") (name "unconnected-(D2G-GPIO3_C7_d-Pad1C7)") (class "Default")
      (node (ref "D2") (pin "1C7") (pinfunction "GPIO3_C7_d_1C7") (pintype "bidirectional+no_connect"))
    )
    (net (code "179") (name "unconnected-(D2G-GPIO4_B3_d-Pad1A6)") (class "Default")
      (node (ref "D2") (pin "1A6") (pinfunction "GPIO4_B3_d_1A6") (pintype "bidirectional"))
    )
    (net (code "180") (name "unconnected-(D46-NC-Pad9)") (class "Default")
      (node (ref "D46") (pin "9") (pinfunction "NC_9") (pintype "passive+no_connect"))
    )
    (net (code "181") (name "unconnected-(D46-NC-Pad30)") (class "Default")
      (node (ref "D46") (pin "30") (pinfunction "NC_30") (pintype "passive+no_connect"))
    )
  )
)
